# rapidisplay.net
KiCad netlist of a schematic drawn in EAGLE
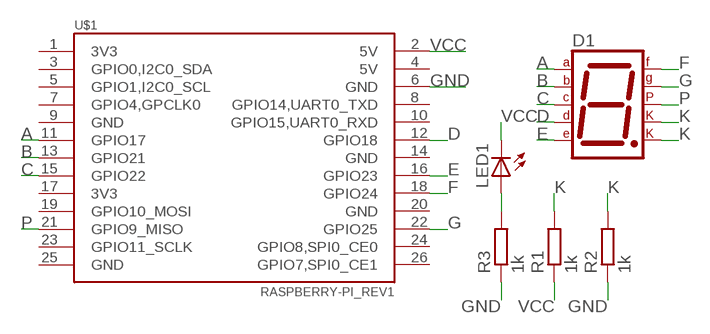
[diagram p0: schematic, sheet 1]

(export (version "E")
  (design (tool "Eeschema 10.0.6"))
  (components
    (comp (ref "D1")
      (value "7SEG-CK")
      (footprint "eagle-import:7SEG-13")
      (libsource (lib "eagle-import") (part "7SEG-CK"))
    )
    (comp (ref "LED1")
      (value "LEDSML1206")
      (footprint "eagle-import:SML1206")
      (libsource (lib "eagle-import") (part "LEDSML1206"))
    )
    (comp (ref "R1")
      (value "1k")
      (footprint "eagle-import:M1206")
      (libsource (lib "eagle-import") (part "R-EU_M1206"))
    )
    (comp (ref "R2")
      (value "1k")
      (footprint "eagle-import:M1206")
      (libsource (lib "eagle-import") (part "R-EU_M1206"))
    )
    (comp (ref "R3")
      (value "1k")
      (footprint "eagle-import:M1206")
      (libsource (lib "eagle-import") (part "R-EU_M1206"))
    )
    (comp (ref "U$1")
      (value "RASPBERRY-PI_REV1")
      (footprint "eagle-import:RASPBERRY-PI_REV1")
      (libsource (lib "eagle-import") (part "RASPBERRY-PI_REV1"))
    )
  )
  (nets
    (net (code "1") (name "/A") (class "Default")
      (node (ref "D1") (pin "7") (pinfunction "A_7") (pintype "passive"))
      (node (ref "U$1") (pin "11") (pinfunction "GPIO17_11") (pintype "bidirectional"))
    )
    (net (code "2") (name "/B") (class "Default")
      (node (ref "D1") (pin "6") (pinfunction "B_6") (pintype "passive"))
      (node (ref "U$1") (pin "13") (pinfunction "GPIO21_13") (pintype "bidirectional"))
    )
    (net (code "3") (name "/C") (class "Default")
      (node (ref "D1") (pin "4") (pinfunction "C_4") (pintype "passive"))
      (node (ref "U$1") (pin "15") (pinfunction "GPIO22_15") (pintype "bidirectional"))
    )
    (net (code "4") (name "/D") (class "Default")
      (node (ref "D1") (pin "2") (pinfunction "D_2") (pintype "passive"))
      (node (ref "U$1") (pin "12") (pinfunction "GPIO18_12") (pintype "bidirectional"))
    )
    (net (code "5") (name "/E") (class "Default")
      (node (ref "D1") (pin "1") (pinfunction "E_1") (pintype "passive"))
      (node (ref "U$1") (pin "16") (pinfunction "GPIO23_16") (pintype "bidirectional"))
    )
    (net (code "6") (name "/F") (class "Default")
      (node (ref "D1") (pin "9") (pinfunction "F_9") (pintype "passive"))
      (node (ref "U$1") (pin "18") (pinfunction "GPIO24_18") (pintype "bidirectional"))
    )
    (net (code "7") (name "/G") (class "Default")
      (node (ref "D1") (pin "10") (pinfunction "G_10") (pintype "passive"))
      (node (ref "U$1") (pin "22") (pinfunction "GPIO25_22") (pintype "bidirectional"))
    )
    (net (code "8") (name "/GND") (class "Default")
      (node (ref "R2") (pin "1") (pinfunction "1_1") (pintype "passive"))
      (node (ref "R3") (pin "1") (pinfunction "1_1") (pintype "passive"))
      (node (ref "U$1") (pin "6") (pinfunction "GND_6") (pintype "bidirectional"))
    )
    (net (code "9") (name "/K") (class "Default")
      (node (ref "D1") (pin "3") (pinfunction "CK1_3") (pintype "passive"))
      (node (ref "D1") (pin "8") (pinfunction "CK2_8") (pintype "passive"))
      (node (ref "R1") (pin "2") (pinfunction "2_2") (pintype "passive"))
      (node (ref "R2") (pin "2") (pinfunction "2_2") (pintype "passive"))
    )
    (net (code "10") (name "/P") (class "Default")
      (node (ref "D1") (pin "5") (pinfunction "DP_5") (pintype "passive"))
      (node (ref "U$1") (pin "21") (pinfunction "GPIO9_MISO_21") (pintype "bidirectional"))
    )
    (net (code "11") (name "/VCC") (class "Default")
      (node (ref "LED1") (pin "C") (pinfunction "C_C") (pintype "passive"))
      (node (ref "R1") (pin "1") (pinfunction "1_1") (pintype "passive"))
      (node (ref "U$1") (pin "2") (pinfunction "5V_2") (pintype "bidirectional"))
    )
    (net (code "12") (name "Net-(LED1-PadA)") (class "Default")
      (node (ref "LED1") (pin "A") (pinfunction "A_A") (pintype "passive"))
      (node (ref "R3") (pin "2") (pinfunction "2_2") (pintype "passive"))
    )
    (net (code "13") (name "unconnected-(U$1-3V3-Pad1)") (class "Default")
      (node (ref "U$1") (pin "1") (pinfunction "3V3_1") (pintype "bidirectional"))
    )
    (net (code "14") (name "unconnected-(U$1-3V3-Pad17)") (class "Default")
      (node (ref "U$1") (pin "17") (pinfunction "3V3_17") (pintype "bidirectional"))
    )
    (net (code "15") (name "unconnected-(U$1-5V-Pad4)") (class "Default")
      (node (ref "U$1") (pin "4") (pinfunction "5V_4") (pintype "bidirectional"))
    )
    (net (code "16") (name "unconnected-(U$1-GND-Pad9)") (class "Default")
      (node (ref "U$1") (pin "9") (pinfunction "GND_9") (pintype "bidirectional"))
    )
    (net (code "17") (name "unconnected-(U$1-GND-Pad14)") (class "Default")
      (node (ref "U$1") (pin "14") (pinfunction "GND_14") (pintype "bidirectional"))
    )
    (net (code "18") (name "unconnected-(U$1-GND-Pad20)") (class "Default")
      (node (ref "U$1") (pin "20") (pinfunction "GND_20") (pintype "bidirectional"))
    )
    (net (code "19") (name "unconnected-(U$1-GND-Pad25)") (class "Default")
      (node (ref "U$1") (pin "25") (pinfunction "GND_25") (pintype "bidirectional"))
    )
    (net (code "20") (name "unconnected-(U$1-GPIO0,I2C0_SDA-Pad3)") (class "Default")
      (node (ref "U$1") (pin "3") (pinfunction "GPIO0,I2C0_SDA_3") (pintype "bidirectional"))
    )
    (net (code "21") (name "unconnected-(U$1-GPIO1,I2C0_SCL-Pad5)") (class "Default")
      (node (ref "U$1") (pin "5") (pinfunction "GPIO1,I2C0_SCL_5") (pintype "bidirectional"))
    )
    (net (code "22") (name "unconnected-(U$1-GPIO4,GPCLK0-Pad7)") (class "Default")
      (node (ref "U$1") (pin "7") (pinfunction "GPIO4,GPCLK0_7") (pintype "bidirectional"))
    )
    (net (code "23") (name "unconnected-(U$1-GPIO7,SPI0_CE1-Pad26)") (class "Default")
      (node (ref "U$1") (pin "26") (pinfunction "GPIO7,SPI0_CE1_26") (pintype "bidirectional"))
    )
    (net (code "24") (name "unconnected-(U$1-GPIO8,SPI0_CE0-Pad24)") (class "Default")
      (node (ref "U$1") (pin "24") (pinfunction "GPIO8,SPI0_CE0_24") (pintype "bidirectional"))
    )
    (net (code "25") (name "unconnected-(U$1-GPIO10_MOSI-Pad19)") (class "Default")
      (node (ref "U$1") (pin "19") (pinfunction "GPIO10_MOSI_19") (pintype "bidirectional"))
    )
    (net (code "26") (name "unconnected-(U$1-GPIO11_SCLK-Pad23)") (class "Default")
      (node (ref "U$1") (pin "23") (pinfunction "GPIO11_SCLK_23") (pintype "bidirectional"))
    )
    (net (code "27") (name "unconnected-(U$1-GPIO14,UART0_TXD-Pad8)") (class "Default")
      (node (ref "U$1") (pin "8") (pinfunction "GPIO14,UART0_TXD_8") (pintype "bidirectional"))
    )
    (net (code "28") (name "unconnected-(U$1-GPIO15,UART0_RXD-Pad10)") (class "Default")
      (node (ref "U$1") (pin "10") (pinfunction "GPIO15,UART0_RXD_10") (pintype "bidirectional"))
    )
  )
)
